# Power2.net
KiCad netlist of a schematic drawn in Altium Designer
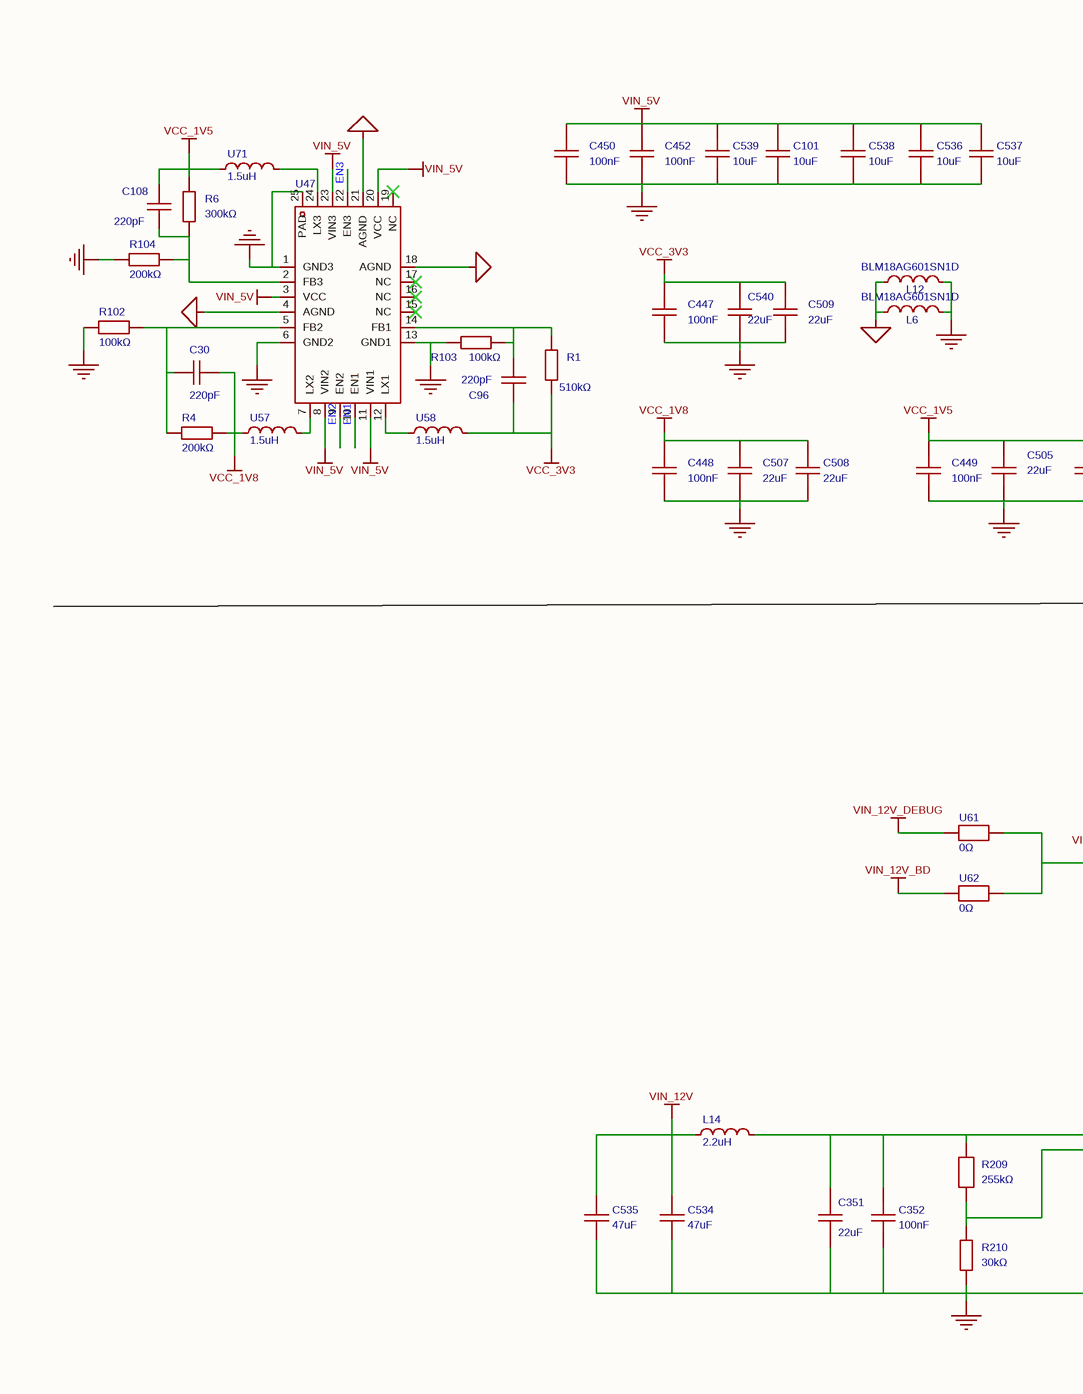
[diagram p0: Power2.schdoc, left]
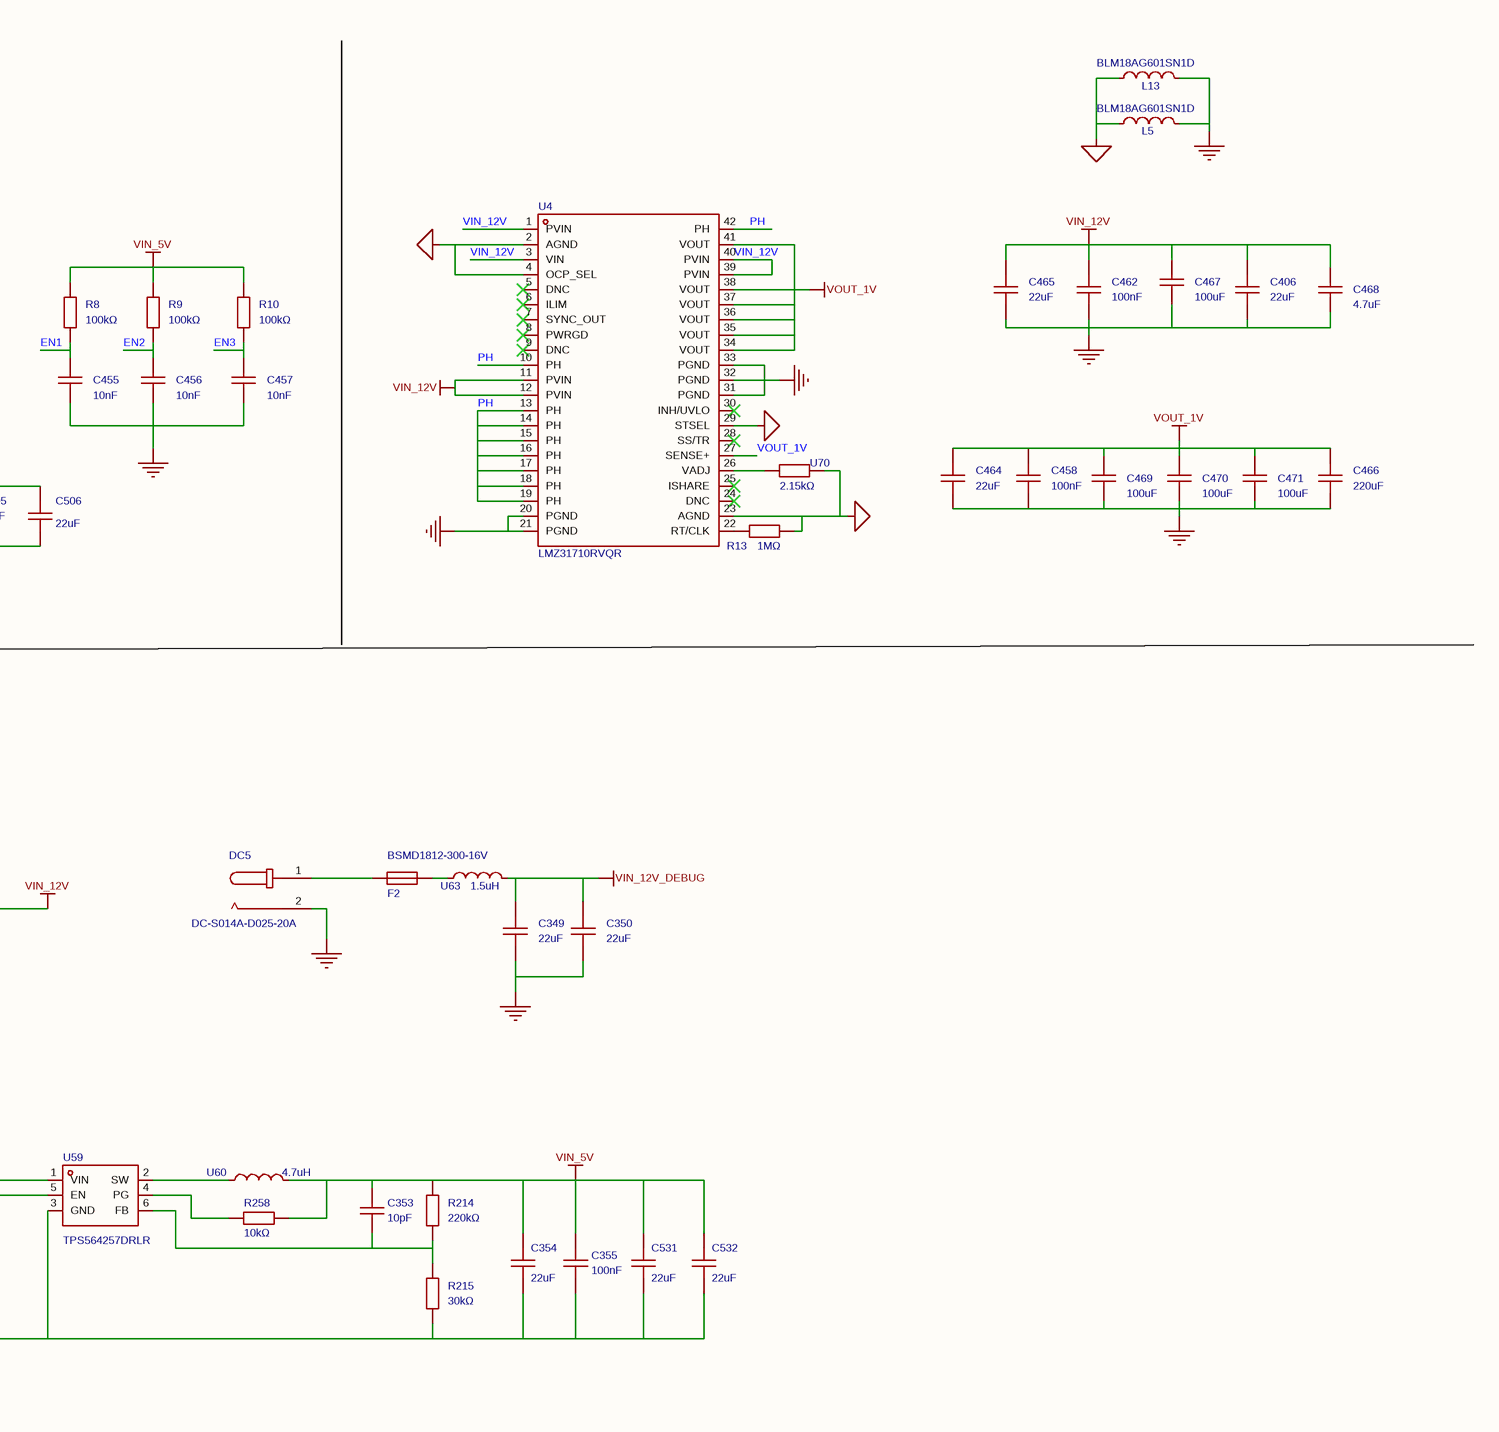
[diagram p1: Power2.schdoc, right]

(export (version "E")
  (design (tool "Eeschema 10.0.6"))
  (components
    (comp (ref "C30")
      (value "220pF")
      (footprint "C0402")
      (description "容值:220pF;精度:±10%;额定电压:50V;材质(温度系数):X7R;")
      (fields (field (name "MANUFACTURER") "FH(风华)") (field (name "MANUFACTURERPART") "0402B221K500NT"))
      (libsource (lib "altium-import") (part "root_2_0402B221K500NT_"))
    )
    (comp (ref "C96")
      (value "220pF")
      (footprint "C0402")
      (description "容值:220pF;精度:±10%;额定电压:50V;材质(温度系数):X7R;")
      (fields (field (name "MANUFACTURER") "FH(风华)") (field (name "MANUFACTURERPART") "0402B221K500NT"))
      (libsource (lib "altium-import") (part "root_1_0402B221K500NT_"))
    )
    (comp (ref "C101")
      (value "10uF")
      (footprint "C0603")
      (description "容值:10uF;精度:±10%;额定电压:10V;材质(温度系数):X5R;")
      (fields
        (field (name "MANUFACTURER") "SAMSUNG(三星)")
        (field (name "MANUFACTURER PART") "CL10A106KP8NNNC")
      )
      (libsource (lib "altium-import") (part "root_1_CL10A106KP8NNNC_"))
    )
    (comp (ref "C108")
      (value "220pF")
      (footprint "C0402")
      (description "容值:220pF;精度:±10%;额定电压:50V;材质(温度系数):X7R;")
      (fields (field (name "MANUFACTURER") "FH(风华)") (field (name "MANUFACTURERPART") "0402B221K500NT"))
      (libsource (lib "altium-import") (part "root_3_0402B221K500NT_"))
    )
    (comp (ref "C349")
      (value "22uF")
      (footprint "C0805")
      (description "容值:22uF;精度:±20%;额定电压:25V;材质(温度系数):X5R;")
      (fields (field (name "MANUFACTURER") "SAMSUNG(三星)") (field (name "MANUFACTURERPART") "CL21A226MAQNNNE"))
      (libsource (lib "altium-import") (part "root_1_CL21A226MAQNNNE_"))
    )
    (comp (ref "C350")
      (value "22uF")
      (footprint "C0805")
      (description "容值:22uF;精度:±20%;额定电压:25V;材质(温度系数):X5R;")
      (fields (field (name "MANUFACTURER") "SAMSUNG(三星)") (field (name "MANUFACTURERPART") "CL21A226MAQNNNE"))
      (libsource (lib "altium-import") (part "root_1_CL21A226MAQNNNE_"))
    )
    (comp (ref "C351")
      (value "22uF")
      (footprint "C0805")
      (description "容值:22uF;精度:±20%;额定电压:25V;材质(温度系数):X5R;")
      (fields (field (name "MANUFACTURER") "SAMSUNG(三星)") (field (name "MANUFACTURERPART") "CL21A226MAQNNNE"))
      (libsource (lib "altium-import") (part "root_1_CL21A226MAQNNNE_"))
    )
    (comp (ref "C352")
      (value "100nF")
      (footprint "C0603")
      (description "容值:100nF;精度:±10%;额定电压:50V;材质(温度系数):X7R;")
      (fields
        (field (name "MANUFACTURER") "YAGEO(国巨)")
        (field (name "MANUFACTURER PART") "CC0603KRX7R9BB104")
      )
      (libsource (lib "altium-import") (part "root_1_CC0603KRX7R9BB104_"))
    )
    (comp (ref "C353")
      (value "10pF")
      (footprint "C0603")
      (description "容值:10pF;精度:±5%;额定电压:50V;材质(温度系数):C0G;")
      (fields
        (field (name "MANUFACTURER PART") "CL10C100JB8NNNC")
        (field (name "MANUFACTURER") "SAMSUNG(三星)")
      )
      (libsource (lib "altium-import") (part "root_1_CL10C100JB8NNNC_"))
    )
    (comp (ref "C354")
      (value "22uF")
      (footprint "C0805")
      (description "容值:22uF;精度:±20%;额定电压:25V;材质(温度系数):X5R;")
      (fields (field (name "MANUFACTURER") "SAMSUNG(三星)") (field (name "MANUFACTURERPART") "CL21A226MAQNNNE"))
      (libsource (lib "altium-import") (part "root_1_CL21A226MAQNNNE_"))
    )
    (comp (ref "C355")
      (value "100nF")
      (footprint "C0603")
      (description "容值:100nF;精度:±10%;额定电压:50V;材质(温度系数):X7R;")
      (fields
        (field (name "MANUFACTURER") "YAGEO(国巨)")
        (field (name "MANUFACTURER PART") "CC0603KRX7R9BB104")
      )
      (libsource (lib "altium-import") (part "root_1_CC0603KRX7R9BB104_"))
    )
    (comp (ref "C406")
      (value "22uF")
      (footprint "C0805")
      (description "容值:22uF;精度:±20%;额定电压:25V;材质(温度系数):X5R;")
      (fields (field (name "MANUFACTURER") "SAMSUNG(三星)") (field (name "MANUFACTURERPART") "CL21A226MAQNNNE"))
      (libsource (lib "altium-import") (part "root_1_CL21A226MAQNNNE_"))
    )
    (comp (ref "C447")
      (value "100nF")
      (footprint "C0402")
      (description "容值:100nF;精度:±10%;额定电压:50V;材质(温度系数):X7R;")
      (fields
        (field (name "MANUFACTURER") "muRata(村田)")
        (field (name "MANUFACTURER PART") "GRM155R71H104KE14D")
      )
      (libsource (lib "altium-import") (part "root_1_GRM155R71H104KE14D_"))
    )
    (comp (ref "C448")
      (value "100nF")
      (footprint "C0402")
      (description "容值:100nF;精度:±10%;额定电压:50V;材质(温度系数):X7R;")
      (fields
        (field (name "MANUFACTURER") "muRata(村田)")
        (field (name "MANUFACTURER PART") "GRM155R71H104KE14D")
      )
      (libsource (lib "altium-import") (part "root_1_GRM155R71H104KE14D_"))
    )
    (comp (ref "C449")
      (value "100nF")
      (footprint "C0402")
      (description "容值:100nF;精度:±10%;额定电压:50V;材质(温度系数):X7R;")
      (fields
        (field (name "MANUFACTURER") "muRata(村田)")
        (field (name "MANUFACTURER PART") "GRM155R71H104KE14D")
      )
      (libsource (lib "altium-import") (part "root_1_GRM155R71H104KE14D_"))
    )
    (comp (ref "C450")
      (value "100nF")
      (footprint "C0402")
      (description "容值:100nF;精度:±10%;额定电压:50V;材质(温度系数):X7R;")
      (fields
        (field (name "MANUFACTURER") "muRata(村田)")
        (field (name "MANUFACTURER PART") "GRM155R71H104KE14D")
      )
      (libsource (lib "altium-import") (part "root_1_GRM155R71H104KE14D_"))
    )
    (comp (ref "C452")
      (value "100nF")
      (footprint "C0402")
      (description "容值:100nF;精度:±10%;额定电压:50V;材质(温度系数):X7R;")
      (fields
        (field (name "MANUFACTURER") "muRata(村田)")
        (field (name "MANUFACTURER PART") "GRM155R71H104KE14D")
      )
      (libsource (lib "altium-import") (part "root_1_GRM155R71H104KE14D_"))
    )
    (comp (ref "C455")
      (value "10nF")
      (footprint "C0402")
      (description "容值:10nF;精度:±10%;额定电压:50V;材质(温度系数):X7R;")
      (fields
        (field (name "MANUFACTURER PART") "CC0402KRX7R9BB103")
        (field (name "MANUFACTURER") "YAGEO(国巨)")
      )
      (libsource (lib "altium-import") (part "root_1_CC0402KRX7R9BB103_"))
    )
    (comp (ref "C456")
      (value "10nF")
      (footprint "C0402")
      (description "容值:10nF;精度:±10%;额定电压:50V;材质(温度系数):X7R;")
      (fields
        (field (name "MANUFACTURER PART") "CC0402KRX7R9BB103")
        (field (name "MANUFACTURER") "YAGEO(国巨)")
      )
      (libsource (lib "altium-import") (part "root_1_CC0402KRX7R9BB103_"))
    )
    (comp (ref "C457")
      (value "10nF")
      (footprint "C0402")
      (description "容值:10nF;精度:±10%;额定电压:50V;材质(温度系数):X7R;")
      (fields
        (field (name "MANUFACTURER PART") "CC0402KRX7R9BB103")
        (field (name "MANUFACTURER") "YAGEO(国巨)")
      )
      (libsource (lib "altium-import") (part "root_1_CC0402KRX7R9BB103_"))
    )
    (comp (ref "C458")
      (value "100nF")
      (footprint "C0402")
      (description "容值:100nF;精度:±10%;额定电压:50V;材质(温度系数):X7R;")
      (fields
        (field (name "MANUFACTURER") "muRata(村田)")
        (field (name "MANUFACTURER PART") "GRM155R71H104KE14D")
      )
      (libsource (lib "altium-import") (part "root_1_GRM155R71H104KE14D_"))
    )
    (comp (ref "C462")
      (value "100nF")
      (footprint "C0402")
      (description "容值:100nF;精度:±10%;额定电压:50V;材质(温度系数):X7R;")
      (fields
        (field (name "MANUFACTURER") "muRata(村田)")
        (field (name "MANUFACTURER PART") "GRM155R71H104KE14D")
      )
      (libsource (lib "altium-import") (part "root_1_GRM155R71H104KE14D_"))
    )
    (comp (ref "C464")
      (value "22uF")
      (footprint "C0603")
      (description "容值:22uF;精度:±20%;额定电压:6.3V;材质(温度系数):X5R;")
      (fields (field (name "MANUFACTURER") "SAMSUNG(三星)") (field (name "MANUFACTURERPART") "CL10A226MQ8NRNC"))
      (libsource (lib "altium-import") (part "root_1_CL10A226MQ8NRNC_"))
    )
    (comp (ref "C465")
      (value "22uF")
      (footprint "C0805")
      (description "容值:22uF;精度:±20%;额定电压:25V;材质(温度系数):X5R;")
      (fields (field (name "MANUFACTURER") "SAMSUNG(三星)") (field (name "MANUFACTURERPART") "CL21A226MAQNNNE"))
      (libsource (lib "altium-import") (part "root_1_CL21A226MAQNNNE_"))
    )
    (comp (ref "C466")
      (value "220uF")
      (footprint "C1206")
      (description "容值:220uF;精度:±20%;额定电压:6.3V;材质(温度系数):X5R;")
      (fields
        (field (name "MANUFACTURER") "muRata(村田)")
        (field (name "MANUFACTURERPART") "GRM31CR60J227ME11L")
      )
      (libsource (lib "altium-import") (part "root_1_GRM31CR60J227ME11L_"))
    )
    (comp (ref "C467")
      (value "100uF")
      (footprint "C1206")
      (description "容值:100uF;精度:±20%;额定电压:6.3V;材质(温度系数):X5R;")
      (fields
        (field (name "MANUFACTURER PART") "CL31A107MQHNNNE")
        (field (name "MANUFACTURER") "SAMSUNG(三星)")
      )
      (libsource (lib "altium-import") (part "root_1_CL31A107MQHNNNE_"))
    )
    (comp (ref "C468")
      (value "4.7uF")
      (footprint "C0603")
      (description "容值:4.7uF;精度:±10%;额定电压:16V;材质(温度系数):X5R;")
      (fields
        (field (name "MANUFACTURER PART") "CL10A475KO8NNNC")
        (field (name "MANUFACTURER") "SAMSUNG(三星)")
      )
      (libsource (lib "altium-import") (part "root_1_CL10A475KO8NNNC_"))
    )
    (comp (ref "C469")
      (value "100uF")
      (footprint "C1206")
      (description "容值:100uF;精度:±20%;额定电压:6.3V;材质(温度系数):X5R;")
      (fields
        (field (name "MANUFACTURER PART") "CL31A107MQHNNNE")
        (field (name "MANUFACTURER") "SAMSUNG(三星)")
      )
      (libsource (lib "altium-import") (part "root_1_CL31A107MQHNNNE_"))
    )
    (comp (ref "C470")
      (value "100uF")
      (footprint "C1206")
      (description "容值:100uF;精度:±20%;额定电压:6.3V;材质(温度系数):X5R;")
      (fields
        (field (name "MANUFACTURER PART") "CL31A107MQHNNNE")
        (field (name "MANUFACTURER") "SAMSUNG(三星)")
      )
      (libsource (lib "altium-import") (part "root_1_CL31A107MQHNNNE_"))
    )
    (comp (ref "C471")
      (value "100uF")
      (footprint "C1206")
      (description "容值:100uF;精度:±20%;额定电压:6.3V;材质(温度系数):X5R;")
      (fields
        (field (name "MANUFACTURER PART") "CL31A107MQHNNNE")
        (field (name "MANUFACTURER") "SAMSUNG(三星)")
      )
      (libsource (lib "altium-import") (part "root_1_CL31A107MQHNNNE_"))
    )
    (comp (ref "C505")
      (value "22uF")
      (footprint "C0805")
      (description "容值:22uF;精度:±20%;额定电压:10V;材质(温度系数):X5R;")
      (fields (field (name "MANUFACTURER") "TDK") (field (name "MANUFACTURERPART") "C2012X5R1A226MT0J0E"))
      (libsource (lib "altium-import") (part "root_0_C2012X5R1A226MT0J0E_"))
    )
    (comp (ref "C506")
      (value "22uF")
      (footprint "C0805")
      (description "容值:22uF;精度:±20%;额定电压:10V;材质(温度系数):X5R;")
      (fields (field (name "MANUFACTURER") "TDK") (field (name "MANUFACTURERPART") "C2012X5R1A226MT0J0E"))
      (libsource (lib "altium-import") (part "root_0_C2012X5R1A226MT0J0E_"))
    )
    (comp (ref "C507")
      (value "22uF")
      (footprint "C0805")
      (description "容值:22uF;精度:±20%;额定电压:10V;材质(温度系数):X5R;")
      (fields (field (name "MANUFACTURER") "TDK") (field (name "MANUFACTURERPART") "C2012X5R1A226MT0J0E"))
      (libsource (lib "altium-import") (part "root_0_C2012X5R1A226MT0J0E_"))
    )
    (comp (ref "C508")
      (value "22uF")
      (footprint "C0805")
      (description "容值:22uF;精度:±20%;额定电压:10V;材质(温度系数):X5R;")
      (fields (field (name "MANUFACTURER") "TDK") (field (name "MANUFACTURERPART") "C2012X5R1A226MT0J0E"))
      (libsource (lib "altium-import") (part "root_0_C2012X5R1A226MT0J0E_"))
    )
    (comp (ref "C509")
      (value "22uF")
      (footprint "C0805")
      (description "容值:22uF;精度:±20%;额定电压:10V;材质(温度系数):X5R;")
      (fields (field (name "MANUFACTURER") "TDK") (field (name "MANUFACTURERPART") "C2012X5R1A226MT0J0E"))
      (libsource (lib "altium-import") (part "root_0_C2012X5R1A226MT0J0E_"))
    )
    (comp (ref "C531")
      (value "22uF")
      (footprint "C0805")
      (description "容值:22uF;精度:±20%;额定电压:25V;材质(温度系数):X5R;")
      (fields (field (name "MANUFACTURER") "SAMSUNG(三星)") (field (name "MANUFACTURERPART") "CL21A226MAQNNNE"))
      (libsource (lib "altium-import") (part "root_1_CL21A226MAQNNNE_"))
    )
    (comp (ref "C532")
      (value "22uF")
      (footprint "C0805")
      (description "容值:22uF;精度:±20%;额定电压:25V;材质(温度系数):X5R;")
      (fields (field (name "MANUFACTURER") "SAMSUNG(三星)") (field (name "MANUFACTURERPART") "CL21A226MAQNNNE"))
      (libsource (lib "altium-import") (part "root_1_CL21A226MAQNNNE_"))
    )
    (comp (ref "C534")
      (value "47uF")
      (footprint "C0603")
      (description "容值:47uF;精度:±20%;额定电压:6.3V;材质(温度系数):X5R;")
      (fields
        (field (name "MANUFACTURER") "muRata(村田)")
        (field (name "MANUFACTURER PART") "GRM188R60J476ME15D")
      )
      (libsource (lib "altium-import") (part "root_1_GRM188R60J476ME15D_"))
    )
    (comp (ref "C535")
      (value "47uF")
      (footprint "C0603")
      (description "容值:47uF;精度:±20%;额定电压:6.3V;材质(温度系数):X5R;")
      (fields
        (field (name "MANUFACTURER") "muRata(村田)")
        (field (name "MANUFACTURER PART") "GRM188R60J476ME15D")
      )
      (libsource (lib "altium-import") (part "root_1_GRM188R60J476ME15D_"))
    )
    (comp (ref "C536")
      (value "10uF")
      (footprint "C0603")
      (description "容值:10uF;精度:±10%;额定电压:10V;材质(温度系数):X5R;")
      (fields
        (field (name "MANUFACTURER") "SAMSUNG(三星)")
        (field (name "MANUFACTURER PART") "CL10A106KP8NNNC")
      )
      (libsource (lib "altium-import") (part "root_1_CL10A106KP8NNNC_"))
    )
    (comp (ref "C537")
      (value "10uF")
      (footprint "C0603")
      (description "容值:10uF;精度:±10%;额定电压:10V;材质(温度系数):X5R;")
      (fields
        (field (name "MANUFACTURER") "SAMSUNG(三星)")
        (field (name "MANUFACTURER PART") "CL10A106KP8NNNC")
      )
      (libsource (lib "altium-import") (part "root_1_CL10A106KP8NNNC_"))
    )
    (comp (ref "C538")
      (value "10uF")
      (footprint "C0603")
      (description "容值:10uF;精度:±10%;额定电压:10V;材质(温度系数):X5R;")
      (fields
        (field (name "MANUFACTURER") "SAMSUNG(三星)")
        (field (name "MANUFACTURER PART") "CL10A106KP8NNNC")
      )
      (libsource (lib "altium-import") (part "root_1_CL10A106KP8NNNC_"))
    )
    (comp (ref "C539")
      (value "10uF")
      (footprint "C0603")
      (description "容值:10uF;精度:±10%;额定电压:10V;材质(温度系数):X5R;")
      (fields
        (field (name "MANUFACTURER") "SAMSUNG(三星)")
        (field (name "MANUFACTURER PART") "CL10A106KP8NNNC")
      )
      (libsource (lib "altium-import") (part "root_1_CL10A106KP8NNNC_"))
    )
    (comp (ref "C540")
      (value "22uF")
      (footprint "C0805")
      (description "容值:22uF;精度:±20%;额定电压:10V;材质(温度系数):X5R;")
      (fields (field (name "MANUFACTURER") "TDK") (field (name "MANUFACTURERPART") "C2012X5R1A226MT0J0E"))
      (libsource (lib "altium-import") (part "root_0_C2012X5R1A226MT0J0E_"))
    )
    (comp (ref "DC5")
      (value "DC-S014A-D025-20A")
      (footprint "DC-IN-TH_DC-S014A-D025-20A")
      (description "连接器类型:DC电源插座;安装方式:弯插;触点内径:2.5mm;触点外径:5.7mm;额定电流:20A;额定电压:30V;工作温度范围:-40℃~+85℃;")
      (fields (field (name "MANUFACTURER") "G-Switch(品赞)"))
      (libsource (lib "altium-import") (part "root_0_DC-S014A-D025-20A_"))
    )
    (comp (ref "F2")
      (value "BSMD1812-300-16V")
      (footprint "F1812")
      (description "最大电压:16V;最大电流:40A;保持电流:3A;跳闸电流:6A;")
      (fields (field (name "MANUFACTURER") "BHFUSE(佰宏)"))
      (libsource (lib "altium-import") (part "root_0_BSMD1812-300-16V_"))
    )
    (comp (ref "L5")
      (value "BLM18AG601SN1D")
      (footprint "L0603")
      (description "标称阻抗@测试频率:600Ω@100MHz;误差:±25%;直流电阻(RDC):380mΩ;")
      (fields (field (name "MANUFACTURER") "muRata(村田)") (field (name "TOLERANCE") "±25%"))
      (libsource (lib "altium-import") (part "root_0_BLM18AG601SN1D_"))
    )
    (comp (ref "L6")
      (value "BLM18AG601SN1D")
      (footprint "L0603")
      (description "标称阻抗@测试频率:600Ω@100MHz;误差:±25%;直流电阻(RDC):380mΩ;")
      (fields (field (name "MANUFACTURER") "muRata(村田)") (field (name "TOLERANCE") "±25%"))
      (libsource (lib "altium-import") (part "root_0_BLM18AG601SN1D_"))
    )
    (comp (ref "L12")
      (value "BLM18AG601SN1D")
      (footprint "L0603")
      (description "标称阻抗@测试频率:600Ω@100MHz;误差:±25%;直流电阻(RDC):380mΩ;")
      (fields (field (name "MANUFACTURER") "muRata(村田)") (field (name "TOLERANCE") "±25%"))
      (libsource (lib "altium-import") (part "root_0_BLM18AG601SN1D_"))
    )
    (comp (ref "L13")
      (value "BLM18AG601SN1D")
      (footprint "L0603")
      (description "标称阻抗@测试频率:600Ω@100MHz;误差:±25%;直流电阻(RDC):380mΩ;")
      (fields (field (name "MANUFACTURER") "muRata(村田)") (field (name "TOLERANCE") "±25%"))
      (libsource (lib "altium-import") (part "root_0_BLM18AG601SN1D_"))
    )
    (comp (ref "L14")
      (value "2.2uH")
      (footprint "IND-SMD_L2.5-W2.0_FWP252012P-2R2ML")
      (description "电感值:2.2uH;精度:±20%;额定电流:2.27A;饱和电流(Isat):3A;类型:一体成型电感;")
      (fields
        (field (name "MANUFACTURER") "cjiang(长江微电)")
        (field (name "MANUFACTURERPART") "FWP252012P-2R2ML")
      )
      (libsource (lib "altium-import") (part "root_0_FWP252012P-2R2ML_"))
    )
    (comp (ref "R1")
      (value "510kΩ")
      (footprint "R0603")
      (description "电阻类型:厚膜电阻;阻值:510kΩ;精度:±1%;功率:100mW;最大工作电压:75V;温度系数:±100ppm/℃;")
      (fields
        (field (name "MANUFACTURER") "UNI-ROYAL(厚声)")
        (field (name "MANUFACTURER PART") "0603WAF5103T5E")
      )
      (libsource (lib "altium-import") (part "root_1_0603WAF5103T5E_"))
    )
    (comp (ref "R4")
      (value "200kΩ")
      (footprint "R0603")
      (description "电阻类型:厚膜电阻;阻值:200kΩ;精度:±1%;功率:100mW;最大工作电压:75V;温度系数:±100ppm/℃;")
      (fields
        (field (name "MANUFACTURER") "UNI-ROYAL(厚声)")
        (field (name "MANUFACTURER PART") "0603WAF2003T5E")
      )
      (libsource (lib "altium-import") (part "root_0_0603WAF2003T5E_"))
    )
    (comp (ref "R6")
      (value "300kΩ")
      (footprint "R0603")
      (description "电阻类型:厚膜电阻;阻值:300kΩ;精度:±1%;功率:100mW;最大工作电压:75V;温度系数:±100ppm/℃;")
      (fields
        (field (name "MANUFACTURER") "UNI-ROYAL(厚声)")
        (field (name "MANUFACTURER PART") "0603WAF3003T5E")
      )
      (libsource (lib "altium-import") (part "root_1_0603WAF3003T5E_"))
    )
    (comp (ref "R8")
      (value "100kΩ")
      (footprint "R0402")
      (description "电阻类型:厚膜电阻;阻值:100kΩ;精度:±1%;功率:62.5mW;最大工作电压:50V;温度系数:±100ppm/℃;")
      (fields (field (name "MANUFACTURER") "YAGEO(国巨)") (field (name "MANUFACTURERPART") "RC0402FR-07100KL"))
      (libsource (lib "altium-import") (part "root_1_RC0402FR-07100KL_"))
    )
    (comp (ref "R9")
      (value "100kΩ")
      (footprint "R0402")
      (description "电阻类型:厚膜电阻;阻值:100kΩ;精度:±1%;功率:62.5mW;最大工作电压:50V;温度系数:±100ppm/℃;")
      (fields (field (name "MANUFACTURER") "YAGEO(国巨)") (field (name "MANUFACTURERPART") "RC0402FR-07100KL"))
      (libsource (lib "altium-import") (part "root_1_RC0402FR-07100KL_"))
    )
    (comp (ref "R10")
      (value "100kΩ")
      (footprint "R0402")
      (description "电阻类型:厚膜电阻;阻值:100kΩ;精度:±1%;功率:62.5mW;最大工作电压:50V;温度系数:±100ppm/℃;")
      (fields (field (name "MANUFACTURER") "YAGEO(国巨)") (field (name "MANUFACTURERPART") "RC0402FR-07100KL"))
      (libsource (lib "altium-import") (part "root_1_RC0402FR-07100KL_"))
    )
    (comp (ref "R13")
      (value "1MΩ")
      (footprint "R0603")
      (description "电阻类型:厚膜电阻;阻值:1MΩ;精度:±1%;功率:100mW;最大工作电压:75V;温度系数:±100ppm/℃;")
      (fields
        (field (name "MANUFACTURER") "UNI-ROYAL(厚声)")
        (field (name "MANUFACTURER PART") "0603WAF1004T5E")
      )
      (libsource (lib "altium-import") (part "root_0_0603WAF1004T5E_"))
    )
    (comp (ref "R102")
      (value "100kΩ")
      (footprint "R0603")
      (description "电阻类型:薄膜电阻;阻值:100kΩ;精度:±0.1%;功率:100mW;最大工作电压:75V;温度系数:±25ppm/℃;")
      (fields (field (name "MANUFACTURER") "YAGEO(国巨)") (field (name "MANUFACTURERPART") "RT0603BRD07100KL"))
      (libsource (lib "altium-import") (part "root_0_RT0603BRD07100KL_"))
    )
    (comp (ref "R103")
      (value "100kΩ")
      (footprint "R0603")
      (description "电阻类型:薄膜电阻;阻值:100kΩ;精度:±0.1%;功率:100mW;最大工作电压:75V;温度系数:±25ppm/℃;")
      (fields (field (name "MANUFACTURER") "YAGEO(国巨)") (field (name "MANUFACTURERPART") "RT0603BRD07100KL"))
      (libsource (lib "altium-import") (part "root_0_RT0603BRD07100KL_"))
    )
    (comp (ref "R104")
      (value "200kΩ")
      (footprint "R0603")
      (description "电阻类型:厚膜电阻;阻值:200kΩ;精度:±1%;功率:100mW;最大工作电压:75V;温度系数:±100ppm/℃;")
      (fields
        (field (name "MANUFACTURER") "UNI-ROYAL(厚声)")
        (field (name "MANUFACTURER PART") "0603WAF2003T5E")
      )
      (libsource (lib "altium-import") (part "root_0_0603WAF2003T5E_"))
    )
    (comp (ref "R209")
      (value "255kΩ")
      (footprint "R0805")
      (description "电阻类型:厚膜电阻;阻值:255kΩ;精度:±1%;功率:125mW;最大工作电压:150V;温度系数:±100ppm/℃;")
      (fields (field (name "MANUFACTURER") "FOJAN(富捷)") (field (name "MANUFACTURER PART") "FRC0805F2553TS"))
      (libsource (lib "altium-import") (part "root_1_FRC0805F2553TS_"))
    )
    (comp (ref "R210")
      (value "30kΩ")
      (footprint "R0805")
      (description "电阻类型:厚膜电阻;阻值:30kΩ;精度:±1%;功率:125mW;最大工作电压:150V;温度系数:±100ppm/℃;")
      (fields
        (field (name "MANUFACTURER") "UNI-ROYAL(厚声)")
        (field (name "MANUFACTURER PART") "0805W8F3002T5E")
      )
      (libsource (lib "altium-import") (part "root_1_0805W8F3002T5E_"))
    )
    (comp (ref "R214")
      (value "220kΩ")
      (footprint "R0805")
      (description "电阻类型:厚膜电阻;阻值:220kΩ;精度:±1%;功率:125mW;最大工作电压:150V;温度系数:±100ppm/℃;")
      (fields
        (field (name "MANUFACTURER") "UNI-ROYAL(厚声)")
        (field (name "MANUFACTURER PART") "0805W8F2203T5E")
      )
      (libsource (lib "altium-import") (part "root_1_0805W8F2203T5E_"))
    )
    (comp (ref "R215")
      (value "30kΩ")
      (footprint "R0805")
      (description "电阻类型:厚膜电阻;阻值:30kΩ;精度:±1%;功率:125mW;最大工作电压:150V;温度系数:±100ppm/℃;")
      (fields
        (field (name "MANUFACTURER") "UNI-ROYAL(厚声)")
        (field (name "MANUFACTURER PART") "0805W8F3002T5E")
      )
      (libsource (lib "altium-import") (part "root_1_0805W8F3002T5E_"))
    )
    (comp (ref "R258")
      (value "10kΩ")
      (footprint "R0603")
      (description "电阻类型:厚膜电阻;阻值:10kΩ;精度:±1%;功率:100mW;最大工作电压:75V;温度系数:±100ppm/℃;")
      (fields
        (field (name "MANUFACTURER") "UNI-ROYAL(厚声)")
        (field (name "MANUFACTURER PART") "0603WAF1002T5E")
      )
      (libsource (lib "altium-import") (part "root_0_0603WAF1002T5E_"))
    )
    (comp (ref "U4")
      (value "LMZ31710RVQR")
      (footprint "B3QFN-42_L10.0-W10.0-P0.80-TL-EP")
      (description "输入电压(DC):2.95V~17V;输出电压:600mV~5.5V;输出电流(最大值):10A;转换效率:94%;")
      (fields (field (name "MANUFACTURER") "TI(德州仪器)"))
      (libsource (lib "altium-import") (part "root_0_LMZ31710RVQR_"))
    )
    (comp (ref "U47")
      (value "EA3059C")
      (footprint "QFN-24_L4.0-W4.0-P0.50-BL-EP2.6")
      (description "电源电压:2.7V~5.5V;最大充电电流:3A;电池类型:-;电池节数:3;")
      (fields (field (name "MANUFACTURER") "everanalog(申风)"))
      (libsource (lib "altium-import") (part "root_0_EA3059C_"))
    )
    (comp (ref "U57")
      (value "1.5uH")
      (footprint "IND-SMD_L2.5-W2.0_YXMBL252010P")
      (description "电感值:1.5uH;精度:±20%;额定电流:2.5A;饱和电流(Isat):3.2A;类型:一体成型电感;")
      (fields
        (field (name "MANUFACTURER") "cjiang(长江微电)")
        (field (name "MANUFACTURERPART") "FWP252012P-1R5ML")
      )
      (libsource (lib "altium-import") (part "root_0_FWP252012P-1R5ML_"))
    )
    (comp (ref "U58")
      (value "1.5uH")
      (footprint "IND-SMD_L2.5-W2.0_YXMBL252010P")
      (description "电感值:1.5uH;精度:±20%;额定电流:2.5A;饱和电流(Isat):3.2A;类型:一体成型电感;")
      (fields
        (field (name "MANUFACTURER") "cjiang(长江微电)")
        (field (name "MANUFACTURERPART") "FWP252012P-1R5ML")
      )
      (libsource (lib "altium-import") (part "root_0_FWP252012P-1R5ML_"))
    )
    (comp (ref "U59")
      (value "TPS564257DRLR")
      (footprint "SOT-563-6_L1.6-W1.2-P0.5-LS1.6-BR")
      (description "TPS564257 3V 至 17V 输入电压、4A FCCM 模式、同步降压转换器")
      (fields (field (name "MANUFACTURER") "TI(德州仪器)"))
      (libsource (lib "altium-import") (part "root_0_TPS564257DRLR_"))
    )
    (comp (ref "U60")
      (value "4.7uH")
      (footprint "IND-SMD_L2.5-W2.0-VLS252012CX-150M")
      (description "电感值:4.7uH;精度:±20%;额定电流:2A;饱和电流(Isat):2.6A;类型:一体成型电感;")
      (fields
        (field (name "MANUFACTURER") "cjiang(长江微电)")
        (field (name "MANUFACTURERPART") "FTC252010S4R7MBCA")
      )
      (libsource (lib "altium-import") (part "root_0_FTC252010S4R7MBCA_"))
    )
    (comp (ref "U61")
      (value "0Ω")
      (footprint "R1812")
      (description "电阻类型:厚膜电阻;阻值:0Ω;精度:±1%;功率:750mW;最大工作电压:200V;")
      (fields (field (name "MANUFACTURER") "FOJAN(富捷)") (field (name "MANUFACTURERPART") "FRC1812F0000TS"))
      (libsource (lib "altium-import") (part "root_0_FRC1812F0000TS_"))
    )
    (comp (ref "U62")
      (value "0Ω")
      (footprint "R1812")
      (description "电阻类型:厚膜电阻;阻值:0Ω;精度:±1%;功率:750mW;最大工作电压:200V;")
      (fields (field (name "MANUFACTURER") "FOJAN(富捷)") (field (name "MANUFACTURERPART") "FRC1812F0000TS"))
      (libsource (lib "altium-import") (part "root_0_FRC1812F0000TS_"))
    )
    (comp (ref "U63")
      (value "1.5uH")
      (footprint "IND-SMD_L2.5-W2.0_YXMBL252010P")
      (description "电感值:1.5uH;精度:±20%;额定电流:2.5A;饱和电流(Isat):3.2A;类型:一体成型电感;")
      (fields
        (field (name "MANUFACTURER") "cjiang(长江微电)")
        (field (name "MANUFACTURERPART") "FWP252012P-1R5ML")
      )
      (libsource (lib "altium-import") (part "root_0_FWP252012P-1R5ML_"))
    )
    (comp (ref "U70")
      (value "2.15kΩ")
      (footprint "R0603")
      (description "电阻类型:薄膜电阻;阻值:2.15kΩ;精度:±0.1%;功率:100mW;温度系数:±50ppm/℃;")
      (fields (field (name "MANUFACTURER") "YAGEO(国巨)") (field (name "MANUFACTURERPART") "RT0603BRE072K15L"))
      (libsource (lib "altium-import") (part "root_0_RT0603BRE072K15L_"))
    )
    (comp (ref "U71")
      (value "1.5uH")
      (footprint "IND-SMD_L2.5-W2.0_YXMBL252010P")
      (description "电感值:1.5uH;精度:±20%;额定电流:2.5A;饱和电流(Isat):3.2A;类型:一体成型电感;")
      (fields
        (field (name "MANUFACTURER") "cjiang(长江微电)")
        (field (name "MANUFACTURERPART") "FWP252012P-1R5ML")
      )
      (libsource (lib "altium-import") (part "root_0_FWP252012P-1R5ML_"))
    )
  )
  (nets
    (net (code "1") (name "/EN1") (class "Default")
      (node (ref "C455") (pin "2") (pinfunction "2_2") (pintype "passive"))
      (node (ref "R8") (pin "1") (pinfunction "1_1") (pintype "passive"))
      (node (ref "U47") (pin "10") (pinfunction "EN1_10") (pintype "passive"))
    )
    (net (code "2") (name "/EN2") (class "Default")
      (node (ref "C456") (pin "2") (pinfunction "2_2") (pintype "passive"))
      (node (ref "R9") (pin "1") (pinfunction "1_1") (pintype "passive"))
      (node (ref "U47") (pin "9") (pinfunction "EN2_9") (pintype "passive"))
    )
    (net (code "3") (name "/EN3") (class "Default")
      (node (ref "C457") (pin "2") (pinfunction "2_2") (pintype "passive"))
      (node (ref "R10") (pin "1") (pinfunction "1_1") (pintype "passive"))
      (node (ref "U47") (pin "22") (pinfunction "EN3_22") (pintype "passive"))
    )
    (net (code "4") (name "/PH") (class "Default")
      (node (ref "U4") (pin "10") (pinfunction "PH_10") (pintype "passive"))
      (node (ref "U4") (pin "13") (pinfunction "PH_13") (pintype "passive"))
      (node (ref "U4") (pin "14") (pinfunction "PH_14") (pintype "passive"))
      (node (ref "U4") (pin "15") (pinfunction "PH_15") (pintype "passive"))
      (node (ref "U4") (pin "16") (pinfunction "PH_16") (pintype "passive"))
      (node (ref "U4") (pin "17") (pinfunction "PH_17") (pintype "passive"))
      (node (ref "U4") (pin "18") (pinfunction "PH_18") (pintype "passive"))
      (node (ref "U4") (pin "19") (pinfunction "PH_19") (pintype "passive"))
      (node (ref "U4") (pin "42") (pinfunction "PH_42") (pintype "passive"))
    )
    (net (code "5") (name "AGND") (class "Default")
      (node (ref "L12") (pin "1") (pinfunction "1_1") (pintype "passive"))
      (node (ref "L13") (pin "1") (pinfunction "1_1") (pintype "passive"))
      (node (ref "L5") (pin "1") (pinfunction "1_1") (pintype "passive"))
      (node (ref "L6") (pin "1") (pinfunction "1_1") (pintype "passive"))
      (node (ref "R13") (pin "2") (pinfunction "2_2") (pintype "passive"))
      (node (ref "U4") (pin "2") (pinfunction "AGND_2") (pintype "passive"))
      (node (ref "U4") (pin "23") (pinfunction "AGND_23") (pintype "passive"))
      (node (ref "U4") (pin "29") (pinfunction "STSEL_29") (pintype "passive"))
      (node (ref "U4") (pin "4") (pinfunction "OCP_SEL_4") (pintype "passive"))
      (node (ref "U47") (pin "18") (pinfunction "AGND_18") (pintype "passive"))
      (node (ref "U47") (pin "21") (pinfunction "AGND_21") (pintype "passive"))
      (node (ref "U47") (pin "4") (pinfunction "AGND_4") (pintype "passive"))
      (node (ref "U70") (pin "2") (pinfunction "2_2") (pintype "passive"))
    )
    (net (code "6") (name "GND") (class "Default")
      (node (ref "C101") (pin "1") (pinfunction "1_1") (pintype "passive"))
      (node (ref "C349") (pin "1") (pinfunction "1_1") (pintype "passive"))
      (node (ref "C350") (pin "1") (pinfunction "1_1") (pintype "passive"))
      (node (ref "C351") (pin "1") (pinfunction "1_1") (pintype "passive"))
      (node (ref "C352") (pin "1") (pinfunction "1_1") (pintype "passive"))
      (node (ref "C354") (pin "1") (pinfunction "1_1") (pintype "passive"))
      (node (ref "C355") (pin "1") (pinfunction "1_1") (pintype "passive"))
      (node (ref "C406") (pin "1") (pinfunction "1_1") (pintype "passive"))
      (node (ref "C447") (pin "1") (pinfunction "1_1") (pintype "passive"))
      (node (ref "C448") (pin "1") (pinfunction "1_1") (pintype "passive"))
      (node (ref "C449") (pin "1") (pinfunction "1_1") (pintype "passive"))
      (node (ref "C450") (pin "1") (pinfunction "1_1") (pintype "passive"))
      (node (ref "C452") (pin "1") (pinfunction "1_1") (pintype "passive"))
      (node (ref "C455") (pin "1") (pinfunction "1_1") (pintype "passive"))
      (node (ref "C456") (pin "1") (pinfunction "1_1") (pintype "passive"))
      (node (ref "C457") (pin "1") (pinfunction "1_1") (pintype "passive"))
      (node (ref "C458") (pin "1") (pinfunction "1_1") (pintype "passive"))
      (node (ref "C462") (pin "1") (pinfunction "1_1") (pintype "passive"))
      (node (ref "C464") (pin "1") (pinfunction "1_1") (pintype "passive"))
      (node (ref "C465") (pin "1") (pinfunction "1_1") (pintype "passive"))
      (node (ref "C466") (pin "1") (pinfunction "1_1") (pintype "passive"))
      (node (ref "C467") (pin "1") (pinfunction "1_1") (pintype "passive"))
      (node (ref "C468") (pin "1") (pinfunction "1_1") (pintype "passive"))
      (node (ref "C469") (pin "1") (pinfunction "1_1") (pintype "passive"))
      (node (ref "C470") (pin "1") (pinfunction "1_1") (pintype "passive"))
      (node (ref "C471") (pin "1") (pinfunction "1_1") (pintype "passive"))
      (node (ref "C505") (pin "1") (pinfunction "1_1") (pintype "passive"))
      (node (ref "C506") (pin "1") (pinfunction "1_1") (pintype "passive"))
      (node (ref "C507") (pin "1") (pinfunction "1_1") (pintype "passive"))
      (node (ref "C508") (pin "1") (pinfunction "1_1") (pintype "passive"))
      (node (ref "C509") (pin "1") (pinfunction "1_1") (pintype "passive"))
      (node (ref "C531") (pin "1") (pinfunction "1_1") (pintype "passive"))
      (node (ref "C532") (pin "1") (pinfunction "1_1") (pintype "passive"))
      (node (ref "C534") (pin "1") (pinfunction "1_1") (pintype "passive"))
      (node (ref "C535") (pin "1") (pinfunction "1_1") (pintype "passive"))
      (node (ref "C536") (pin "1") (pinfunction "1_1") (pintype "passive"))
      (node (ref "C537") (pin "1") (pinfunction "1_1") (pintype "passive"))
      (node (ref "C538") (pin "1") (pinfunction "1_1") (pintype "passive"))
      (node (ref "C539") (pin "1") (pinfunction "1_1") (pintype "passive"))
      (node (ref "C540") (pin "1") (pinfunction "1_1") (pintype "passive"))
      (node (ref "DC5") (pin "2") (pinfunction "2_2") (pintype "passive"))
      (node (ref "L12") (pin "2") (pinfunction "2_2") (pintype "passive"))
      (node (ref "L13") (pin "2") (pinfunction "2_2") (pintype "passive"))
      (node (ref "L5") (pin "2") (pinfunction "2_2") (pintype "passive"))
      (node (ref "L6") (pin "2") (pinfunction "2_2") (pintype "passive"))
      (node (ref "R102") (pin "1") (pinfunction "1_1") (pintype "passive"))
      (node (ref "R103") (pin "1") (pinfunction "1_1") (pintype "passive"))
      (node (ref "R104") (pin "1") (pinfunction "1_1") (pintype "passive"))
      (node (ref "R210") (pin "1") (pinfunction "1_1") (pintype "passive"))
      (node (ref "R215") (pin "1") (pinfunction "1_1") (pintype "passive"))
      (node (ref "U4") (pin "20") (pinfunction "PGND_20") (pintype "passive"))
      (node (ref "U4") (pin "21") (pinfunction "PGND_21") (pintype "passive"))
      (node (ref "U4") (pin "31") (pinfunction "PGND_31") (pintype "passive"))
      (node (ref "U4") (pin "32") (pinfunction "PGND_32") (pintype "passive"))
      (node (ref "U4") (pin "33") (pinfunction "PGND_33") (pintype "passive"))
      (node (ref "U47") (pin "1") (pinfunction "GND3_1") (pintype "passive"))
      (node (ref "U47") (pin "13") (pinfunction "GND1_13") (pintype "passive"))
      (node (ref "U47") (pin "25") (pinfunction "PAD_25") (pintype "passive"))
      (node (ref "U47") (pin "6") (pinfunction "GND2_6") (pintype "passive"))
      (node (ref "U59") (pin "3") (pinfunction "GND_3") (pintype "passive"))
    )
    (net (code "7") (name "Net-(DC5-Pad1)") (class "Default")
      (node (ref "DC5") (pin "1") (pinfunction "1_1") (pintype "passive"))
      (node (ref "F2") (pin "1") (pinfunction "1_1") (pintype "passive"))
    )
    (net (code "8") (name "Net-(F2-Pad2)") (class "Default")
      (node (ref "F2") (pin "2") (pinfunction "2_2") (pintype "passive"))
      (node (ref "U63") (pin "1") (pinfunction "1_1") (pintype "passive"))
    )
    (net (code "9") (name "Net-(U4-RT{slash}CLK)") (class "Default")
      (node (ref "R13") (pin "1") (pinfunction "1_1") (pintype "passive"))
      (node (ref "U4") (pin "22") (pinfunction "RT/CLK_22") (pintype "passive"))
    )
    (net (code "10") (name "Net-(U4-VADJ)") (class "Default")
      (node (ref "U4") (pin "26") (pinfunction "VADJ_26") (pintype "passive"))
      (node (ref "U70") (pin "1") (pinfunction "1_1") (pintype "passive"))
    )
    (net (code "11") (name "Net-(U47-FB1)") (class "Default")
      (node (ref "C96") (pin "2") (pinfunction "2_2") (pintype "passive"))
      (node (ref "R1") (pin "2") (pinfunction "2_2") (pintype "passive"))
      (node (ref "R103") (pin "2") (pinfunction "2_2") (pintype "passive"))
      (node (ref "U47") (pin "14") (pinfunction "FB1_14") (pintype "passive"))
    )
    (net (code "12") (name "Net-(U47-FB2)") (class "Default")
      (node (ref "C30") (pin "2") (pinfunction "2_2") (pintype "passive"))
      (node (ref "R102") (pin "2") (pinfunction "2_2") (pintype "passive"))
      (node (ref "R4") (pin "1") (pinfunction "1_1") (pintype "passive"))
      (node (ref "U47") (pin "5") (pinfunction "FB2_5") (pintype "passive"))
    )
    (net (code "13") (name "Net-(U47-FB3)") (class "Default")
      (node (ref "C108") (pin "2") (pinfunction "2_2") (pintype "passive"))
      (node (ref "R104") (pin "2") (pinfunction "2_2") (pintype "passive"))
      (node (ref "R6") (pin "1") (pinfunction "1_1") (pintype "passive"))
      (node (ref "U47") (pin "2") (pinfunction "FB3_2") (pintype "passive"))
    )
    (net (code "14") (name "Net-(U47-LX1)") (class "Default")
      (node (ref "U47") (pin "12") (pinfunction "LX1_12") (pintype "passive"))
      (node (ref "U58") (pin "1") (pinfunction "1_1") (pintype "passive"))
    )
    (net (code "15") (name "Net-(U47-LX2)") (class "Default")
      (node (ref "U47") (pin "7") (pinfunction "LX2_7") (pintype "passive"))
      (node (ref "U57") (pin "2") (pinfunction "2_2") (pintype "passive"))
    )
    (net (code "16") (name "Net-(U47-LX3)") (class "Default")
      (node (ref "U47") (pin "24") (pinfunction "LX3_24") (pintype "passive"))
      (node (ref "U71") (pin "2") (pinfunction "2_2") (pintype "passive"))
    )
    (net (code "17") (name "Net-(U59-EN)") (class "Default")
      (node (ref "R209") (pin "1") (pinfunction "1_1") (pintype "passive"))
      (node (ref "R210") (pin "2") (pinfunction "2_2") (pintype "passive"))
      (node (ref "U59") (pin "5") (pinfunction "EN_5") (pintype "passive"))
    )
    (net (code "18") (name "Net-(U59-FB)") (class "Default")
      (node (ref "C353") (pin "1") (pinfunction "1_1") (pintype "passive"))
      (node (ref "R214") (pin "1") (pinfunction "1_1") (pintype "passive"))
      (node (ref "R215") (pin "2") (pinfunction "2_2") (pintype "passive"))
      (node (ref "U59") (pin "6") (pinfunction "FB_6") (pintype "passive"))
    )
    (net (code "19") (name "Net-(U59-PG)") (class "Default")
      (node (ref "R258") (pin "1") (pinfunction "1_1") (pintype "passive"))
      (node (ref "U59") (pin "4") (pinfunction "PG_4") (pintype "passive"))
    )
    (net (code "20") (name "Net-(U59-SW)") (class "Default")
      (node (ref "U59") (pin "2") (pinfunction "SW_2") (pintype "passive"))
      (node (ref "U60") (pin "1") (pinfunction "1_1") (pintype "passive"))
    )
    (net (code "21") (name "Net-(U59-VIN)") (class "Default")
      (node (ref "C351") (pin "2") (pinfunction "2_2") (pintype "passive"))
      (node (ref "C352") (pin "2") (pinfunction "2_2") (pintype "passive"))
      (node (ref "L14") (pin "2") (pinfunction "2_2") (pintype "passive"))
      (node (ref "R209") (pin "2") (pinfunction "2_2") (pintype "passive"))
      (node (ref "U59") (pin "1") (pinfunction "VIN_1") (pintype "passive"))
    )
    (net (code "22") (name "VCC_1V5") (class "Default")
      (node (ref "C108") (pin "1") (pinfunction "1_1") (pintype "passive"))
      (node (ref "C449") (pin "2") (pinfunction "2_2") (pintype "passive"))
      (node (ref "C505") (pin "2") (pinfunction "2_2") (pintype "passive"))
      (node (ref "C506") (pin "2") (pinfunction "2_2") (pintype "passive"))
      (node (ref "R6") (pin "2") (pinfunction "2_2") (pintype "passive"))
      (node (ref "U71") (pin "1") (pinfunction "1_1") (pintype "passive"))
    )
    (net (code "23") (name "VCC_1V8") (class "Default")
      (node (ref "C30") (pin "1") (pinfunction "1_1") (pintype "passive"))
      (node (ref "C448") (pin "2") (pinfunction "2_2") (pintype "passive"))
      (node (ref "C507") (pin "2") (pinfunction "2_2") (pintype "passive"))
      (node (ref "C508") (pin "2") (pinfunction "2_2") (pintype "passive"))
      (node (ref "R4") (pin "2") (pinfunction "2_2") (pintype "passive"))
      (node (ref "U57") (pin "1") (pinfunction "1_1") (pintype "passive"))
    )
    (net (code "24") (name "VCC_3V3") (class "Default")
      (node (ref "C447") (pin "2") (pinfunction "2_2") (pintype "passive"))
      (node (ref "C509") (pin "2") (pinfunction "2_2") (pintype "passive"))
      (node (ref "C540") (pin "2") (pinfunction "2_2") (pintype "passive"))
      (node (ref "C96") (pin "1") (pinfunction "1_1") (pintype "passive"))
      (node (ref "R1") (pin "1") (pinfunction "1_1") (pintype "passive"))
      (node (ref "U58") (pin "2") (pinfunction "2_2") (pintype "passive"))
    )
    (net (code "25") (name "VIN_5V") (class "Default")
      (node (ref "C101") (pin "2") (pinfunction "2_2") (pintype "passive"))
      (node (ref "C353") (pin "2") (pinfunction "2_2") (pintype "passive"))
      (node (ref "C354") (pin "2") (pinfunction "2_2") (pintype "passive"))
      (node (ref "C355") (pin "2") (pinfunction "2_2") (pintype "passive"))
      (node (ref "C450") (pin "2") (pinfunction "2_2") (pintype "passive"))
      (node (ref "C452") (pin "2") (pinfunction "2_2") (pintype "passive"))
      (node (ref "C531") (pin "2") (pinfunction "2_2") (pintype "passive"))
      (node (ref "C532") (pin "2") (pinfunction "2_2") (pintype "passive"))
      (node (ref "C536") (pin "2") (pinfunction "2_2") (pintype "passive"))
      (node (ref "C537") (pin "2") (pinfunction "2_2") (pintype "passive"))
      (node (ref "C538") (pin "2") (pinfunction "2_2") (pintype "passive"))
      (node (ref "C539") (pin "2") (pinfunction "2_2") (pintype "passive"))
      (node (ref "R10") (pin "2") (pinfunction "2_2") (pintype "passive"))
      (node (ref "R214") (pin "2") (pinfunction "2_2") (pintype "passive"))
      (node (ref "R258") (pin "2") (pinfunction "2_2") (pintype "passive"))
      (node (ref "R8") (pin "2") (pinfunction "2_2") (pintype "passive"))
      (node (ref "R9") (pin "2") (pinfunction "2_2") (pintype "passive"))
      (node (ref "U47") (pin "11") (pinfunction "VIN1_11") (pintype "passive"))
      (node (ref "U47") (pin "20") (pinfunction "VCC_20") (pintype "passive"))
      (node (ref "U47") (pin "23") (pinfunction "VIN3_23") (pintype "passive"))
      (node (ref "U47") (pin "3") (pinfunction "VCC_3") (pintype "passive"))
      (node (ref "U47") (pin "8") (pinfunction "VIN2_8") (pintype "passive"))
      (node (ref "U60") (pin "2") (pinfunction "2_2") (pintype "passive"))
    )
    (net (code "26") (name "VIN_12V") (class "Default")
      (node (ref "C406") (pin "2") (pinfunction "2_2") (pintype "passive"))
      (node (ref "C462") (pin "2") (pinfunction "2_2") (pintype "passive"))
      (node (ref "C465") (pin "2") (pinfunction "2_2") (pintype "passive"))
      (node (ref "C467") (pin "2") (pinfunction "2_2") (pintype "passive"))
      (node (ref "C468") (pin "2") (pinfunction "2_2") (pintype "passive"))
      (node (ref "C534") (pin "2") (pinfunction "2_2") (pintype "passive"))
      (node (ref "C535") (pin "2") (pinfunction "2_2") (pintype "passive"))
      (node (ref "L14") (pin "1") (pinfunction "1_1") (pintype "passive"))
      (node (ref "U4") (pin "1") (pinfunction "PVIN_1") (pintype "passive"))
      (node (ref "U4") (pin "11") (pinfunction "PVIN_11") (pintype "passive"))
      (node (ref "U4") (pin "12") (pinfunction "PVIN_12") (pintype "passive"))
      (node (ref "U4") (pin "3") (pinfunction "VIN_3") (pintype "passive"))
      (node (ref "U4") (pin "39") (pinfunction "PVIN_39") (pintype "passive"))
      (node (ref "U4") (pin "40") (pinfunction "PVIN_40") (pintype "passive"))
      (node (ref "U61") (pin "2") (pinfunction "2_2") (pintype "passive"))
      (node (ref "U62") (pin "2") (pinfunction "2_2") (pintype "passive"))
    )
    (net (code "27") (name "VIN_12V_BD") (class "Default")
      (node (ref "U62") (pin "1") (pinfunction "1_1") (pintype "passive"))
    )
    (net (code "28") (name "VIN_12V_DEBUG") (class "Default")
      (node (ref "C349") (pin "2") (pinfunction "2_2") (pintype "passive"))
      (node (ref "C350") (pin "2") (pinfunction "2_2") (pintype "passive"))
      (node (ref "U61") (pin "1") (pinfunction "1_1") (pintype "passive"))
      (node (ref "U63") (pin "2") (pinfunction "2_2") (pintype "passive"))
    )
    (net (code "29") (name "VOUT_1V") (class "Default")
      (node (ref "C458") (pin "2") (pinfunction "2_2") (pintype "passive"))
      (node (ref "C464") (pin "2") (pinfunction "2_2") (pintype "passive"))
      (node (ref "C466") (pin "2") (pinfunction "2_2") (pintype "passive"))
      (node (ref "C469") (pin "2") (pinfunction "2_2") (pintype "passive"))
      (node (ref "C470") (pin "2") (pinfunction "2_2") (pintype "passive"))
      (node (ref "C471") (pin "2") (pinfunction "2_2") (pintype "passive"))
      (node (ref "U4") (pin "27") (pinfunction "SENSE+_27") (pintype "passive"))
      (node (ref "U4") (pin "34") (pinfunction "VOUT_34") (pintype "passive"))
      (node (ref "U4") (pin "35") (pinfunction "VOUT_35") (pintype "passive"))
      (node (ref "U4") (pin "36") (pinfunction "VOUT_36") (pintype "passive"))
      (node (ref "U4") (pin "37") (pinfunction "VOUT_37") (pintype "passive"))
      (node (ref "U4") (pin "38") (pinfunction "VOUT_38") (pintype "passive"))
      (node (ref "U4") (pin "41") (pinfunction "VOUT_41") (pintype "passive"))
    )
    (net (code "30") (name "unconnected-(U4-DNC-Pad5)") (class "Default")
      (node (ref "U4") (pin "5") (pinfunction "DNC_5") (pintype "passive+no_connect"))
    )
    (net (code "31") (name "unconnected-(U4-DNC-Pad9)") (class "Default")
      (node (ref "U4") (pin "9") (pinfunction "DNC_9") (pintype "passive+no_connect"))
    )
    (net (code "32") (name "unconnected-(U4-DNC-Pad24)") (class "Default")
      (node (ref "U4") (pin "24") (pinfunction "DNC_24") (pintype "passive+no_connect"))
    )
    (net (code "33") (name "unconnected-(U4-ILIM-Pad6)") (class "Default")
      (node (ref "U4") (pin "6") (pinfunction "ILIM_6") (pintype "passive+no_connect"))
    )
    (net (code "34") (name "unconnected-(U4-INH{slash}UVLO-Pad30)") (class "Default")
      (node (ref "U4") (pin "30") (pinfunction "INH/UVLO_30") (pintype "passive+no_connect"))
    )
    (net (code "35") (name "unconnected-(U4-ISHARE-Pad25)") (class "Default")
      (node (ref "U4") (pin "25") (pinfunction "ISHARE_25") (pintype "passive+no_connect"))
    )
    (net (code "36") (name "unconnected-(U4-PWRGD-Pad8)") (class "Default")
      (node (ref "U4") (pin "8") (pinfunction "PWRGD_8") (pintype "passive+no_connect"))
    )
    (net (code "37") (name "unconnected-(U4-SS{slash}TR-Pad28)") (class "Default")
      (node (ref "U4") (pin "28") (pinfunction "SS/TR_28") (pintype "passive+no_connect"))
    )
    (net (code "38") (name "unconnected-(U4-SYNC_OUT-Pad7)") (class "Default")
      (node (ref "U4") (pin "7") (pinfunction "SYNC_OUT_7") (pintype "passive+no_connect"))
    )
    (net (code "39") (name "unconnected-(U47-NC-Pad15)") (class "Default")
      (node (ref "U47") (pin "15") (pinfunction "NC_15") (pintype "passive+no_connect"))
    )
    (net (code "40") (name "unconnected-(U47-NC-Pad16)") (class "Default")
      (node (ref "U47") (pin "16") (pinfunction "NC_16") (pintype "passive+no_connect"))
    )
    (net (code "41") (name "unconnected-(U47-NC-Pad17)") (class "Default")
      (node (ref "U47") (pin "17") (pinfunction "NC_17") (pintype "passive+no_connect"))
    )
    (net (code "42") (name "unconnected-(U47-NC-Pad19)") (class "Default")
      (node (ref "U47") (pin "19") (pinfunction "NC_19") (pintype "passive+no_connect"))
    )
  )
)
